# ATEMconsole-slider.net
KiCad netlist of a schematic drawn in EAGLE
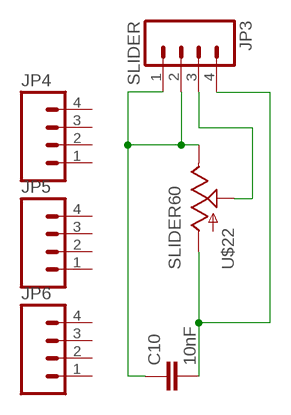
[diagram p0: schematic, sheet 1]

(export (version "E")
  (design (tool "Eeschema 10.0.6"))
  (components
    (comp (ref "C10")
      (value "10nF")
      (footprint "eagle-import:AXIAL-5MM")
      (libsource (lib "eagle-import") (part "CAP_"))
    )
    (comp (ref "JP3")
      (value "SLIDER")
      (footprint "eagle-import:1X04")
      (libsource (lib "eagle-import") (part "M04PTH"))
    )
    (comp (ref "JP4")
      (value "M04PTH")
      (footprint "eagle-import:1X04")
      (libsource (lib "eagle-import") (part "M04PTH"))
    )
    (comp (ref "JP5")
      (value "M04PTH")
      (footprint "eagle-import:1X04")
      (libsource (lib "eagle-import") (part "M04PTH"))
    )
    (comp (ref "JP6")
      (value "M04PTH")
      (footprint "eagle-import:1X04")
      (libsource (lib "eagle-import") (part "M04PTH"))
    )
    (comp (ref "U$22")
      (value "SLIDER60")
      (footprint "eagle-import:SLIDER60")
      (libsource (lib "eagle-import") (part "SLIDER60"))
    )
  )
  (nets
    (net (code "1") (name "Net-(C10-1)") (class "Default")
      (node (ref "C10") (pin "P$1") (pinfunction "1_P$1") (pintype "passive"))
      (node (ref "JP3") (pin "1") (pinfunction "1_1") (pintype "passive"))
      (node (ref "JP3") (pin "2") (pinfunction "2_2") (pintype "passive"))
      (node (ref "U$22") (pin "1") (pinfunction "E_1") (pintype "passive"))
    )
    (net (code "2") (name "Net-(C10-2)") (class "Default")
      (node (ref "C10") (pin "P$2") (pinfunction "2_P$2") (pintype "passive"))
      (node (ref "JP3") (pin "4") (pinfunction "4_4") (pintype "passive"))
      (node (ref "U$22") (pin "3") (pinfunction "A_3") (pintype "passive"))
    )
    (net (code "3") (name "Net-(U$22-S)") (class "Default")
      (node (ref "JP3") (pin "3") (pinfunction "3_3") (pintype "passive"))
      (node (ref "U$22") (pin "2A") (pinfunction "S_2A") (pintype "passive"))
    )
    (net (code "4") (name "unconnected-(JP4-Pad1)") (class "Default")
      (node (ref "JP4") (pin "1") (pinfunction "1_1") (pintype "passive"))
    )
    (net (code "5") (name "unconnected-(JP4-Pad2)") (class "Default")
      (node (ref "JP4") (pin "2") (pinfunction "2_2") (pintype "passive"))
    )
    (net (code "6") (name "unconnected-(JP4-Pad3)") (class "Default")
      (node (ref "JP4") (pin "3") (pinfunction "3_3") (pintype "passive"))
    )
    (net (code "7") (name "unconnected-(JP4-Pad4)") (class "Default")
      (node (ref "JP4") (pin "4") (pinfunction "4_4") (pintype "passive"))
    )
    (net (code "8") (name "unconnected-(JP5-Pad1)") (class "Default")
      (node (ref "JP5") (pin "1") (pinfunction "1_1") (pintype "passive"))
    )
    (net (code "9") (name "unconnected-(JP5-Pad2)") (class "Default")
      (node (ref "JP5") (pin "2") (pinfunction "2_2") (pintype "passive"))
    )
    (net (code "10") (name "unconnected-(JP5-Pad3)") (class "Default")
      (node (ref "JP5") (pin "3") (pinfunction "3_3") (pintype "passive"))
    )
    (net (code "11") (name "unconnected-(JP5-Pad4)") (class "Default")
      (node (ref "JP5") (pin "4") (pinfunction "4_4") (pintype "passive"))
    )
    (net (code "12") (name "unconnected-(JP6-Pad1)") (class "Default")
      (node (ref "JP6") (pin "1") (pinfunction "1_1") (pintype "passive"))
    )
    (net (code "13") (name "unconnected-(JP6-Pad2)") (class "Default")
      (node (ref "JP6") (pin "2") (pinfunction "2_2") (pintype "passive"))
    )
    (net (code "14") (name "unconnected-(JP6-Pad3)") (class "Default")
      (node (ref "JP6") (pin "3") (pinfunction "3_3") (pintype "passive"))
    )
    (net (code "15") (name "unconnected-(JP6-Pad4)") (class "Default")
      (node (ref "JP6") (pin "4") (pinfunction "4_4") (pintype "passive"))
    )
  )
)
